# LCD.net
KiCad netlist of a schematic drawn in EAGLE
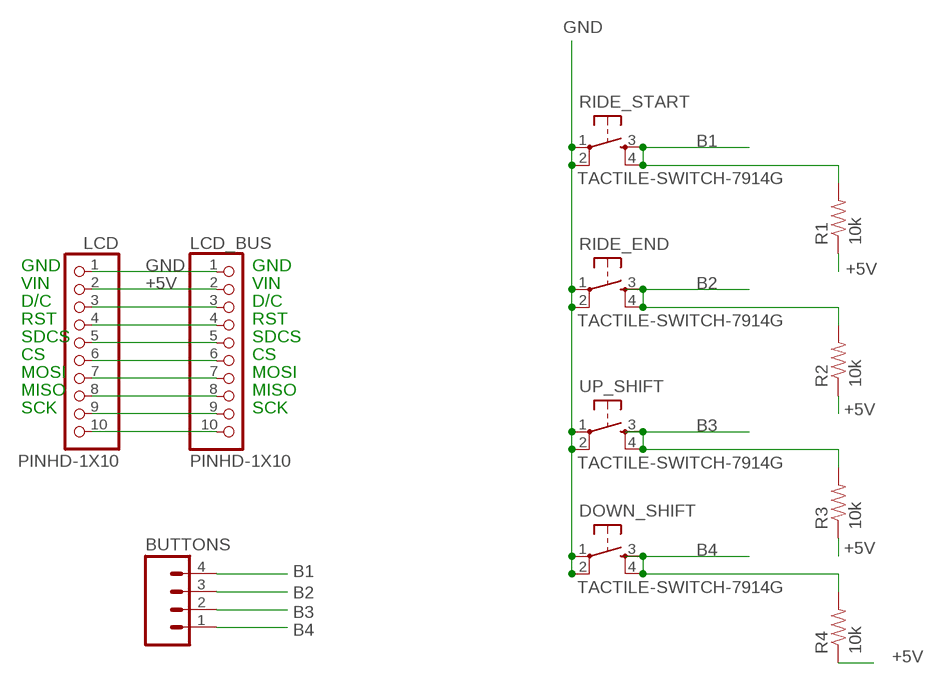
[diagram p0: schematic, sheet 1]

(export (version "E")
  (design (tool "Eeschema 10.0.6"))
  (components
    (comp (ref "BUTTONS")
      (value "M04LONGPADS")
      (footprint "eagle-import:1X04_LONGPADS")
      (libsource (lib "eagle-import") (part "M04LONGPADS"))
    )
    (comp (ref "DOWN_SHIFT")
      (value "TACTILE-SWITCH-7914G")
      (footprint "eagle-import:7914G")
      (libsource (lib "eagle-import") (part "TACTILE-SWITCH-7914G"))
    )
    (comp (ref "LCD")
      (value "PINHD-1X10")
      (footprint "eagle-import:1X10-BIG")
      (libsource (lib "eagle-import") (part "PINHD-1X10"))
    )
    (comp (ref "LCD_BUS")
      (value "PINHD-1X10")
      (footprint "eagle-import:1X10-BIG")
      (libsource (lib "eagle-import") (part "PINHD-1X10"))
    )
    (comp (ref "R1")
      (value "10k")
      (footprint "eagle-import:0805")
      (libsource (lib "eagle-import") (part "RESISTOR0805-RES"))
    )
    (comp (ref "R2")
      (value "10k")
      (footprint "eagle-import:0805")
      (libsource (lib "eagle-import") (part "RESISTOR0805-RES"))
    )
    (comp (ref "R3")
      (value "10k")
      (footprint "eagle-import:0805")
      (libsource (lib "eagle-import") (part "RESISTOR0805-RES"))
    )
    (comp (ref "R4")
      (value "10k")
      (footprint "eagle-import:0805")
      (libsource (lib "eagle-import") (part "RESISTOR0805-RES"))
    )
    (comp (ref "RIDE_END")
      (value "TACTILE-SWITCH-7914G")
      (footprint "eagle-import:7914G")
      (libsource (lib "eagle-import") (part "TACTILE-SWITCH-7914G"))
    )
    (comp (ref "RIDE_START")
      (value "TACTILE-SWITCH-7914G")
      (footprint "eagle-import:7914G")
      (libsource (lib "eagle-import") (part "TACTILE-SWITCH-7914G"))
    )
    (comp (ref "UP_SHIFT")
      (value "TACTILE-SWITCH-7914G")
      (footprint "eagle-import:7914G")
      (libsource (lib "eagle-import") (part "TACTILE-SWITCH-7914G"))
    )
  )
  (nets
    (net (code "1") (name "/+5V") (class "Default")
      (node (ref "LCD") (pin "2") (pinfunction "2_2") (pintype "passive"))
      (node (ref "LCD_BUS") (pin "2") (pinfunction "2_2") (pintype "passive"))
      (node (ref "R1") (pin "1") (pinfunction "1_1") (pintype "passive"))
      (node (ref "R2") (pin "1") (pinfunction "1_1") (pintype "passive"))
      (node (ref "R3") (pin "1") (pinfunction "1_1") (pintype "passive"))
      (node (ref "R4") (pin "1") (pinfunction "1_1") (pintype "passive"))
    )
    (net (code "2") (name "/B1") (class "Default")
      (node (ref "BUTTONS") (pin "4") (pinfunction "4_4") (pintype "passive"))
      (node (ref "R1") (pin "2") (pinfunction "2_2") (pintype "passive"))
      (node (ref "RIDE_START") (pin "3") (pinfunction "3_3") (pintype "passive"))
      (node (ref "RIDE_START") (pin "4") (pinfunction "4_4") (pintype "passive"))
    )
    (net (code "3") (name "/B2") (class "Default")
      (node (ref "BUTTONS") (pin "3") (pinfunction "3_3") (pintype "passive"))
      (node (ref "R2") (pin "2") (pinfunction "2_2") (pintype "passive"))
      (node (ref "RIDE_END") (pin "3") (pinfunction "3_3") (pintype "passive"))
      (node (ref "RIDE_END") (pin "4") (pinfunction "4_4") (pintype "passive"))
    )
    (net (code "4") (name "/B3") (class "Default")
      (node (ref "BUTTONS") (pin "2") (pinfunction "2_2") (pintype "passive"))
      (node (ref "R3") (pin "2") (pinfunction "2_2") (pintype "passive"))
      (node (ref "UP_SHIFT") (pin "3") (pinfunction "3_3") (pintype "passive"))
      (node (ref "UP_SHIFT") (pin "4") (pinfunction "4_4") (pintype "passive"))
    )
    (net (code "5") (name "/B4") (class "Default")
      (node (ref "BUTTONS") (pin "1") (pinfunction "1_1") (pintype "passive"))
      (node (ref "DOWN_SHIFT") (pin "3") (pinfunction "3_3") (pintype "passive"))
      (node (ref "DOWN_SHIFT") (pin "4") (pinfunction "4_4") (pintype "passive"))
      (node (ref "R4") (pin "2") (pinfunction "2_2") (pintype "passive"))
    )
    (net (code "6") (name "/GND") (class "Default")
      (node (ref "DOWN_SHIFT") (pin "1") (pinfunction "1_1") (pintype "passive"))
      (node (ref "DOWN_SHIFT") (pin "2") (pinfunction "2_2") (pintype "passive"))
      (node (ref "LCD") (pin "1") (pinfunction "1_1") (pintype "passive"))
      (node (ref "LCD_BUS") (pin "1") (pinfunction "1_1") (pintype "passive"))
      (node (ref "RIDE_END") (pin "1") (pinfunction "1_1") (pintype "passive"))
      (node (ref "RIDE_END") (pin "2") (pinfunction "2_2") (pintype "passive"))
      (node (ref "RIDE_START") (pin "1") (pinfunction "1_1") (pintype "passive"))
      (node (ref "RIDE_START") (pin "2") (pinfunction "2_2") (pintype "passive"))
      (node (ref "UP_SHIFT") (pin "1") (pinfunction "1_1") (pintype "passive"))
      (node (ref "UP_SHIFT") (pin "2") (pinfunction "2_2") (pintype "passive"))
    )
    (net (code "7") (name "Net-(LCD-Pad3)") (class "Default")
      (node (ref "LCD") (pin "3") (pinfunction "3_3") (pintype "passive"))
      (node (ref "LCD_BUS") (pin "3") (pinfunction "3_3") (pintype "passive"))
    )
    (net (code "8") (name "Net-(LCD-Pad4)") (class "Default")
      (node (ref "LCD") (pin "4") (pinfunction "4_4") (pintype "passive"))
      (node (ref "LCD_BUS") (pin "4") (pinfunction "4_4") (pintype "passive"))
    )
    (net (code "9") (name "Net-(LCD-Pad5)") (class "Default")
      (node (ref "LCD") (pin "5") (pinfunction "5_5") (pintype "passive"))
      (node (ref "LCD_BUS") (pin "5") (pinfunction "5_5") (pintype "passive"))
    )
    (net (code "10") (name "Net-(LCD-Pad6)") (class "Default")
      (node (ref "LCD") (pin "6") (pinfunction "6_6") (pintype "passive"))
      (node (ref "LCD_BUS") (pin "6") (pinfunction "6_6") (pintype "passive"))
    )
    (net (code "11") (name "Net-(LCD-Pad7)") (class "Default")
      (node (ref "LCD") (pin "7") (pinfunction "7_7") (pintype "passive"))
      (node (ref "LCD_BUS") (pin "7") (pinfunction "7_7") (pintype "passive"))
    )
    (net (code "12") (name "Net-(LCD-Pad8)") (class "Default")
      (node (ref "LCD") (pin "8") (pinfunction "8_8") (pintype "passive"))
      (node (ref "LCD_BUS") (pin "8") (pinfunction "8_8") (pintype "passive"))
    )
    (net (code "13") (name "Net-(LCD-Pad9)") (class "Default")
      (node (ref "LCD") (pin "9") (pinfunction "9_9") (pintype "passive"))
      (node (ref "LCD_BUS") (pin "9") (pinfunction "9_9") (pintype "passive"))
    )
    (net (code "14") (name "Net-(LCD-Pad10)") (class "Default")
      (node (ref "LCD") (pin "10") (pinfunction "10_10") (pintype "passive"))
      (node (ref "LCD_BUS") (pin "10") (pinfunction "10_10") (pintype "passive"))
    )
  )
)
